# Sheet1.net
KiCad netlist of a schematic drawn in Altium Designer
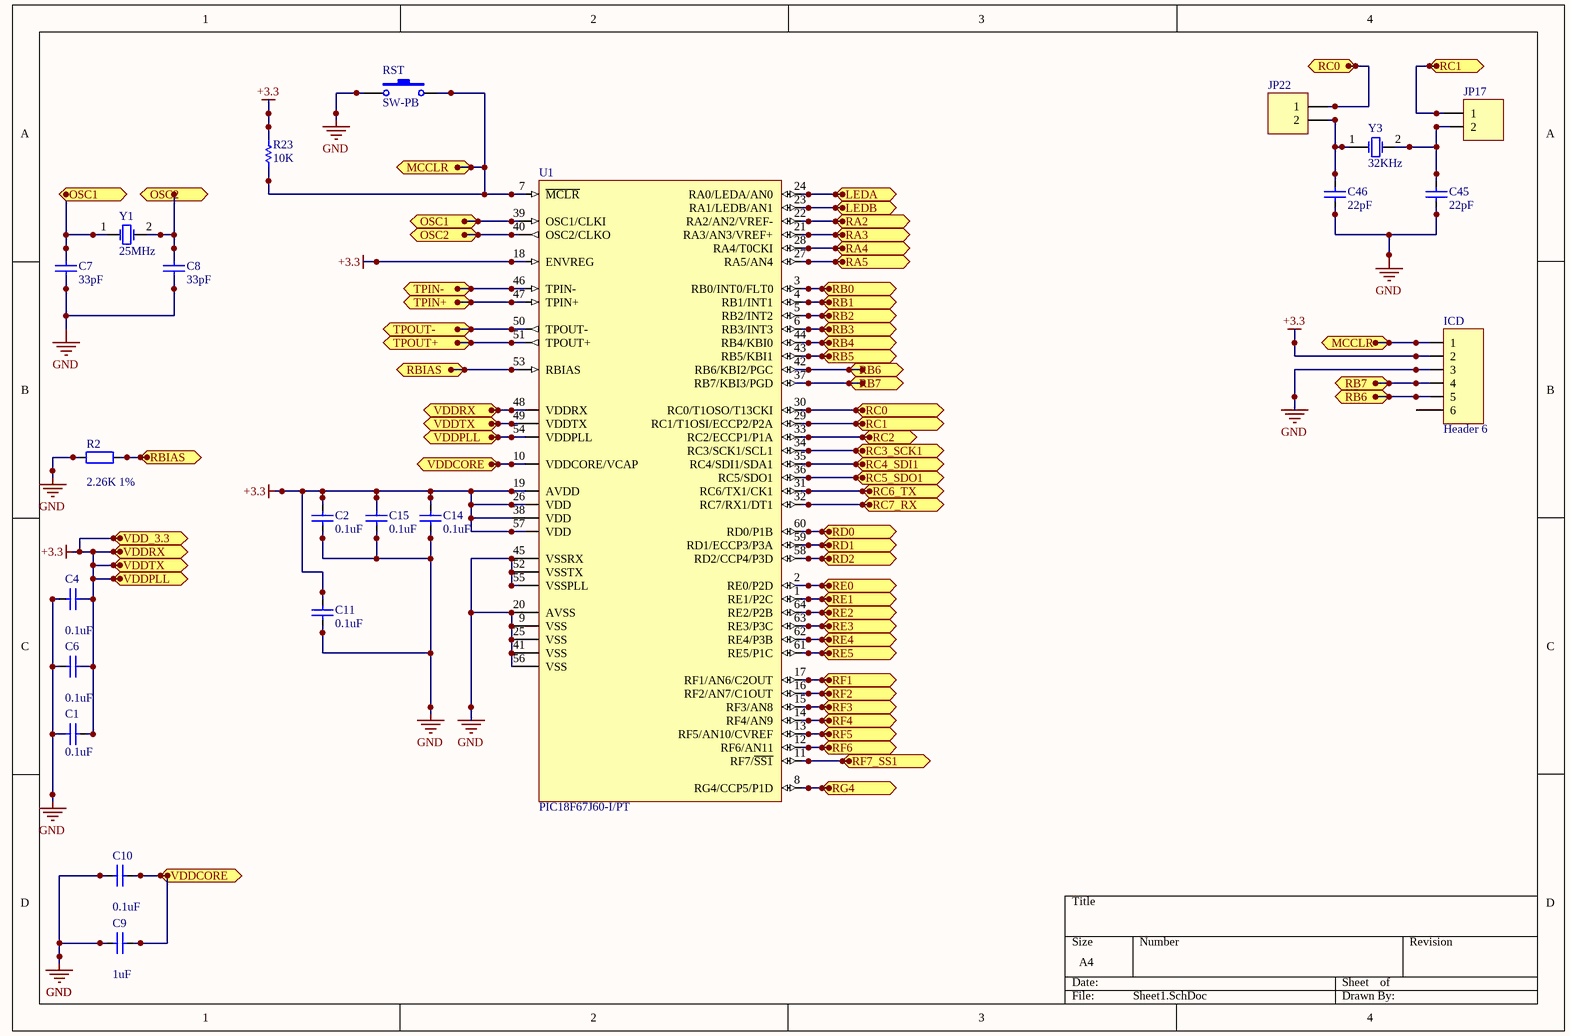
[diagram p0: Sheet1.SchDoc]

(export (version "E")
  (design (tool "Eeschema 10.0.6"))
  (components
    (comp (ref "C1")
      (value "0.1uF")
      (footprint "CAPC2012L")
      (description "Capacitor (Semiconductor SIM Model)")
      (fields (field (name "PUBLISHER") "Altium Limited"))
      (libsource (lib "Miscellaneous Devices") (part "Cap Semi"))
    )
    (comp (ref "C2")
      (value "0.1uF")
      (footprint "CAPC2012L")
      (description "Capacitor")
      (fields (field (name "PUBLISHER") "Altium Limited"))
      (libsource (lib "Miscellaneous Devices") (part "Cap"))
    )
    (comp (ref "C4")
      (value "0.1uF")
      (footprint "CAPC2012L")
      (description "Capacitor")
      (fields (field (name "PUBLISHER") "Altium Limited"))
      (libsource (lib "Miscellaneous Devices") (part "Cap"))
    )
    (comp (ref "C6")
      (value "0.1uF")
      (footprint "CAPC2012L")
      (description "Capacitor")
      (fields (field (name "PUBLISHER") "Altium Limited"))
      (libsource (lib "Miscellaneous Devices") (part "Cap"))
    )
    (comp (ref "C7")
      (value "33pF")
      (footprint "CAPC2012L")
      (description "Capacitor")
      (fields (field (name "PUBLISHER") "Altium Limited"))
      (libsource (lib "Miscellaneous Devices") (part "Cap"))
    )
    (comp (ref "C8")
      (value "33pF")
      (footprint "CAPC2012L")
      (description "Capacitor")
      (fields (field (name "PUBLISHER") "Altium Limited"))
      (libsource (lib "Miscellaneous Devices") (part "Cap"))
    )
    (comp (ref "C9")
      (value "1uF")
      (footprint "CAPC2012L")
      (description "Capacitor")
      (fields (field (name "PUBLISHER") "Altium Limited"))
      (libsource (lib "Miscellaneous Devices") (part "Cap"))
    )
    (comp (ref "C10")
      (value "0.1uF")
      (footprint "CAPC2012L")
      (description "Capacitor")
      (fields (field (name "PUBLISHER") "Altium Limited"))
      (libsource (lib "Miscellaneous Devices") (part "Cap"))
    )
    (comp (ref "C11")
      (value "0.1uF")
      (footprint "CAPC2012L")
      (description "Capacitor")
      (fields (field (name "PUBLISHER") "Altium Limited"))
      (libsource (lib "Miscellaneous Devices") (part "Cap"))
    )
    (comp (ref "C14")
      (value "0.1uF")
      (footprint "CAPC2012L")
      (description "Capacitor")
      (fields (field (name "PUBLISHER") "Altium Limited"))
      (libsource (lib "Miscellaneous Devices") (part "Cap"))
    )
    (comp (ref "C15")
      (value "0.1uF")
      (footprint "CAPC2012L")
      (description "Capacitor")
      (fields (field (name "PUBLISHER") "Altium Limited"))
      (libsource (lib "Miscellaneous Devices") (part "Cap"))
    )
    (comp (ref "C45")
      (value "22pF")
      (footprint "CAPC2012L")
      (description "Capacitor (Semiconductor SIM Model)")
      (fields (field (name "PUBLISHER") "Altium Limited"))
      (libsource (lib "Miscellaneous Devices") (part "Cap Semi"))
    )
    (comp (ref "C46")
      (value "22pF")
      (footprint "CAPC2012L")
      (description "Capacitor (Semiconductor SIM Model)")
      (fields (field (name "PUBLISHER") "Altium Limited"))
      (libsource (lib "Miscellaneous Devices") (part "Cap Semi"))
    )
    (comp (ref "ICD")
      (value "Header 6")
      (footprint "HDR1X6")
      (description "Header, 6-Pin")
      (fields (field (name "PUBLISHER") "Altium Limited"))
      (libsource (lib "Miscellaneous Connectors") (part "Header 6"))
    )
    (comp (ref "JP17")
      (value "Header 2")
      (footprint "HDR1X2")
      (description "Header, 2-Pin")
      (fields (field (name "PUBLISHER") "Altium Limited"))
      (libsource (lib "Miscellaneous Connectors") (part "Header 2"))
    )
    (comp (ref "JP22")
      (value "Header 2")
      (footprint "HDR1X2")
      (description "Header, 2-Pin")
      (fields (field (name "PUBLISHER") "Altium Limited"))
      (libsource (lib "") (part "Header 2_1"))
    )
    (comp (ref "R2")
      (value "2.26K 1%")
      (footprint "RESC2012L")
      (description "Resistor")
      (fields (field (name "PUBLISHER") "Altium Limited"))
      (libsource (lib "Miscellaneous Devices") (part "Res2"))
    )
    (comp (ref "R23")
      (value "10K")
      (footprint "RESC3216L")
      (description "Semiconductor Resistor")
      (fields (field (name "PUBLISHER") "Altium Limited"))
      (libsource (lib "Miscellaneous Devices") (part "Res Semi"))
    )
    (comp (ref "RST")
      (value "SW-PB")
      (footprint "SPST-2")
      (description "Switch")
      (fields (field (name "PUBLISHER") "Altium Limited"))
      (libsource (lib "Miscellaneous Devices") (part "SW-PB"))
    )
    (comp (ref "U1")
      (value "PIC18F67J60-I/PT")
      (footprint "TQFP-PT64_L")
      (fields (field (name "PUBLISHER") "Altium Limited"))
      (libsource (lib "Microchip Microcontroller 8-Bit PIC18") (part "PIC18F67J60-I/PT"))
    )
    (comp (ref "Y1")
      (value "25MHz")
      (footprint "SPST-2")
      (description "Crystal Oscillator")
      (fields (field (name "PUBLISHER") "Altium Limited"))
      (libsource (lib "Miscellaneous Devices") (part "XTAL"))
    )
    (comp (ref "Y3")
      (value "32KHz")
      (footprint "SPST-2")
      (description "Crystal Oscillator")
      (fields (field (name "PUBLISHER") "Altium Limited"))
      (libsource (lib "Miscellaneous Devices") (part "XTAL"))
    )
  )
  (nets
    (net (code "1") (name "+3.3") (class "Default")
      (node (ref "C1") (pin "2") (pinfunction "2_2") (pintype "passive"))
      (node (ref "C11") (pin "2") (pinfunction "2_2") (pintype "passive"))
      (node (ref "C14") (pin "2") (pinfunction "2_2") (pintype "passive"))
      (node (ref "C15") (pin "2") (pinfunction "2_2") (pintype "passive"))
      (node (ref "C2") (pin "2") (pinfunction "2_2") (pintype "passive"))
      (node (ref "C4") (pin "2") (pinfunction "2_2") (pintype "passive"))
      (node (ref "C6") (pin "2") (pinfunction "2_2") (pintype "passive"))
      (node (ref "ICD") (pin "2") (pinfunction "2_2") (pintype "passive"))
      (node (ref "R23") (pin "2") (pinfunction "2_2") (pintype "passive"))
      (node (ref "U1") (pin "18") (pinfunction "ENVREG_18") (pintype "input"))
      (node (ref "U1") (pin "19") (pinfunction "AVDD_19") (pintype "power_in"))
      (node (ref "U1") (pin "26") (pinfunction "VDD_26") (pintype "power_in"))
      (node (ref "U1") (pin "38") (pinfunction "VDD_38") (pintype "power_in"))
      (node (ref "U1") (pin "48") (pinfunction "VDDRX_48") (pintype "power_in"))
      (node (ref "U1") (pin "49") (pinfunction "VDDTX_49") (pintype "power_in"))
      (node (ref "U1") (pin "54") (pinfunction "VDDPLL_54") (pintype "power_in"))
      (node (ref "U1") (pin "57") (pinfunction "VDD_57") (pintype "power_in"))
    )
    (net (code "2") (name "/LEDA") (class "Default")
      (node (ref "U1") (pin "24") (pinfunction "RA0/LEDA/AN0_24") (pintype "bidirectional"))
    )
    (net (code "3") (name "/LEDB") (class "Default")
      (node (ref "U1") (pin "23") (pinfunction "RA1/LEDB/AN1_23") (pintype "bidirectional"))
    )
    (net (code "4") (name "/MCCLR") (class "Default")
      (node (ref "ICD") (pin "1") (pinfunction "1_1") (pintype "passive"))
      (node (ref "R23") (pin "1") (pinfunction "1_1") (pintype "passive"))
      (node (ref "RST") (pin "2") (pinfunction "2_2") (pintype "passive"))
      (node (ref "U1") (pin "7") (pinfunction "~{MCLR}_7") (pintype "input"))
    )
    (net (code "5") (name "/OSC1") (class "Default")
      (node (ref "U1") (pin "39") (pinfunction "OSC1/CLKI_39") (pintype "input"))
    )
    (net (code "6") (name "/OSC2") (class "Default")
      (node (ref "U1") (pin "40") (pinfunction "OSC2/CLKO_40") (pintype "output"))
    )
    (net (code "7") (name "/RA2") (class "Default")
      (node (ref "U1") (pin "22") (pinfunction "RA2/AN2/VREF-_22") (pintype "bidirectional"))
    )
    (net (code "8") (name "/RA3") (class "Default")
      (node (ref "U1") (pin "21") (pinfunction "RA3/AN3/VREF+_21") (pintype "bidirectional"))
    )
    (net (code "9") (name "/RA4") (class "Default")
      (node (ref "U1") (pin "28") (pinfunction "RA4/T0CKI_28") (pintype "bidirectional"))
    )
    (net (code "10") (name "/RA5") (class "Default")
      (node (ref "U1") (pin "27") (pinfunction "RA5/AN4_27") (pintype "bidirectional"))
    )
    (net (code "11") (name "/RB0") (class "Default")
      (node (ref "U1") (pin "3") (pinfunction "RB0/INT0/FLT0_3") (pintype "bidirectional"))
    )
    (net (code "12") (name "/RB1") (class "Default")
      (node (ref "U1") (pin "4") (pinfunction "RB1/INT1_4") (pintype "bidirectional"))
    )
    (net (code "13") (name "/RB2") (class "Default")
      (node (ref "U1") (pin "5") (pinfunction "RB2/INT2_5") (pintype "bidirectional"))
    )
    (net (code "14") (name "/RB3") (class "Default")
      (node (ref "U1") (pin "6") (pinfunction "RB3/INT3_6") (pintype "bidirectional"))
    )
    (net (code "15") (name "/RB4") (class "Default")
      (node (ref "U1") (pin "44") (pinfunction "RB4/KBI0_44") (pintype "bidirectional"))
    )
    (net (code "16") (name "/RB5") (class "Default")
      (node (ref "U1") (pin "43") (pinfunction "RB5/KBI1_43") (pintype "bidirectional"))
    )
    (net (code "17") (name "/RB6") (class "Default")
      (node (ref "ICD") (pin "5") (pinfunction "5_5") (pintype "passive"))
      (node (ref "U1") (pin "42") (pinfunction "RB6/KBI2/PGC_42") (pintype "bidirectional"))
    )
    (net (code "18") (name "/RB7") (class "Default")
      (node (ref "ICD") (pin "4") (pinfunction "4_4") (pintype "passive"))
      (node (ref "U1") (pin "37") (pinfunction "RB7/KBI3/PGD_37") (pintype "bidirectional"))
    )
    (net (code "19") (name "/RBIAS") (class "Default")
      (node (ref "R2") (pin "2") (pinfunction "2_2") (pintype "passive"))
      (node (ref "U1") (pin "53") (pinfunction "RBIAS_53") (pintype "input"))
    )
    (net (code "20") (name "/RC0") (class "Default")
      (node (ref "JP22") (pin "1") (pinfunction "1_1") (pintype "passive"))
      (node (ref "U1") (pin "30") (pinfunction "RC0/T1OSO/T13CKI_30") (pintype "bidirectional"))
    )
    (net (code "21") (name "/RC1") (class "Default")
      (node (ref "JP17") (pin "1") (pinfunction "1_1") (pintype "passive"))
      (node (ref "U1") (pin "29") (pinfunction "RC1/T1OSI/ECCP2/P2A_29") (pintype "bidirectional"))
    )
    (net (code "22") (name "/RC2") (class "Default")
      (node (ref "U1") (pin "33") (pinfunction "RC2/ECCP1/P1A_33") (pintype "bidirectional"))
    )
    (net (code "23") (name "/RC3_SCK1") (class "Default")
      (node (ref "U1") (pin "34") (pinfunction "RC3/SCK1/SCL1_34") (pintype "bidirectional"))
    )
    (net (code "24") (name "/RC4_SDI1") (class "Default")
      (node (ref "U1") (pin "35") (pinfunction "RC4/SDI1/SDA1_35") (pintype "bidirectional"))
    )
    (net (code "25") (name "/RC5_SDO1") (class "Default")
      (node (ref "U1") (pin "36") (pinfunction "RC5/SDO1_36") (pintype "bidirectional"))
    )
    (net (code "26") (name "/RC6_TX") (class "Default")
      (node (ref "U1") (pin "31") (pinfunction "RC6/TX1/CK1_31") (pintype "bidirectional"))
    )
    (net (code "27") (name "/RC7_RX") (class "Default")
      (node (ref "U1") (pin "32") (pinfunction "RC7/RX1/DT1_32") (pintype "bidirectional"))
    )
    (net (code "28") (name "/RD0") (class "Default")
      (node (ref "U1") (pin "60") (pinfunction "RD0/P1B_60") (pintype "bidirectional"))
    )
    (net (code "29") (name "/RD1") (class "Default")
      (node (ref "U1") (pin "59") (pinfunction "RD1/ECCP3/P3A_59") (pintype "bidirectional"))
    )
    (net (code "30") (name "/RD2") (class "Default")
      (node (ref "U1") (pin "58") (pinfunction "RD2/CCP4/P3D_58") (pintype "bidirectional"))
    )
    (net (code "31") (name "/RE0") (class "Default")
      (node (ref "U1") (pin "2") (pinfunction "RE0/P2D_2") (pintype "bidirectional"))
    )
    (net (code "32") (name "/RE1") (class "Default")
      (node (ref "U1") (pin "1") (pinfunction "RE1/P2C_1") (pintype "bidirectional"))
    )
    (net (code "33") (name "/RE2") (class "Default")
      (node (ref "U1") (pin "64") (pinfunction "RE2/P2B_64") (pintype "bidirectional"))
    )
    (net (code "34") (name "/RE3") (class "Default")
      (node (ref "U1") (pin "63") (pinfunction "RE3/P3C_63") (pintype "bidirectional"))
    )
    (net (code "35") (name "/RE4") (class "Default")
      (node (ref "U1") (pin "62") (pinfunction "RE4/P3B_62") (pintype "bidirectional"))
    )
    (net (code "36") (name "/RE5") (class "Default")
      (node (ref "U1") (pin "61") (pinfunction "RE5/P1C_61") (pintype "bidirectional"))
    )
    (net (code "37") (name "/RF1") (class "Default")
      (node (ref "U1") (pin "17") (pinfunction "RF1/AN6/C2OUT_17") (pintype "bidirectional"))
    )
    (net (code "38") (name "/RF2") (class "Default")
      (node (ref "U1") (pin "16") (pinfunction "RF2/AN7/C1OUT_16") (pintype "bidirectional"))
    )
    (net (code "39") (name "/RF3") (class "Default")
      (node (ref "U1") (pin "15") (pinfunction "RF3/AN8_15") (pintype "bidirectional"))
    )
    (net (code "40") (name "/RF4") (class "Default")
      (node (ref "U1") (pin "14") (pinfunction "RF4/AN9_14") (pintype "bidirectional"))
    )
    (net (code "41") (name "/RF5") (class "Default")
      (node (ref "U1") (pin "13") (pinfunction "RF5/AN10/CVREF_13") (pintype "bidirectional"))
    )
    (net (code "42") (name "/RF6") (class "Default")
      (node (ref "U1") (pin "12") (pinfunction "RF6/AN11_12") (pintype "bidirectional"))
    )
    (net (code "43") (name "/RF7_SS1") (class "Default")
      (node (ref "U1") (pin "11") (pinfunction "RF7/~{SS1}_11") (pintype "bidirectional"))
    )
    (net (code "44") (name "/RG4") (class "Default")
      (node (ref "U1") (pin "8") (pinfunction "RG4/CCP5/P1D_8") (pintype "bidirectional"))
    )
    (net (code "45") (name "/TPIN+") (class "Default")
      (node (ref "U1") (pin "47") (pinfunction "TPIN+_47") (pintype "input"))
    )
    (net (code "46") (name "/TPIN-") (class "Default")
      (node (ref "U1") (pin "46") (pinfunction "TPIN-_46") (pintype "input"))
    )
    (net (code "47") (name "/TPOUT+") (class "Default")
      (node (ref "U1") (pin "51") (pinfunction "TPOUT+_51") (pintype "output"))
    )
    (net (code "48") (name "/TPOUT-") (class "Default")
      (node (ref "U1") (pin "50") (pinfunction "TPOUT-_50") (pintype "output"))
    )
    (net (code "49") (name "/VDDCORE") (class "Default")
      (node (ref "C10") (pin "2") (pinfunction "2_2") (pintype "passive"))
      (node (ref "C9") (pin "2") (pinfunction "2_2") (pintype "passive"))
      (node (ref "U1") (pin "10") (pinfunction "VDDCORE/VCAP_10") (pintype "power_in"))
    )
    (net (code "50") (name "GND") (class "Default")
      (node (ref "C1") (pin "1") (pinfunction "1_1") (pintype "passive"))
      (node (ref "C10") (pin "1") (pinfunction "1_1") (pintype "passive"))
      (node (ref "C11") (pin "1") (pinfunction "1_1") (pintype "passive"))
      (node (ref "C14") (pin "1") (pinfunction "1_1") (pintype "passive"))
      (node (ref "C15") (pin "1") (pinfunction "1_1") (pintype "passive"))
      (node (ref "C2") (pin "1") (pinfunction "1_1") (pintype "passive"))
      (node (ref "C4") (pin "1") (pinfunction "1_1") (pintype "passive"))
      (node (ref "C45") (pin "1") (pinfunction "1_1") (pintype "passive"))
      (node (ref "C46") (pin "1") (pinfunction "1_1") (pintype "passive"))
      (node (ref "C6") (pin "1") (pinfunction "1_1") (pintype "passive"))
      (node (ref "C7") (pin "1") (pinfunction "1_1") (pintype "passive"))
      (node (ref "C8") (pin "1") (pinfunction "1_1") (pintype "passive"))
      (node (ref "C9") (pin "1") (pinfunction "1_1") (pintype "passive"))
      (node (ref "ICD") (pin "3") (pinfunction "3_3") (pintype "passive"))
      (node (ref "R2") (pin "1") (pinfunction "1_1") (pintype "passive"))
      (node (ref "RST") (pin "1") (pinfunction "1_1") (pintype "passive"))
      (node (ref "U1") (pin "20") (pinfunction "AVSS_20") (pintype "power_in"))
      (node (ref "U1") (pin "25") (pinfunction "VSS_25") (pintype "power_in"))
      (node (ref "U1") (pin "41") (pinfunction "VSS_41") (pintype "power_in"))
      (node (ref "U1") (pin "45") (pinfunction "VSSRX_45") (pintype "power_in"))
      (node (ref "U1") (pin "52") (pinfunction "VSSTX_52") (pintype "power_in"))
      (node (ref "U1") (pin "55") (pinfunction "VSSPLL_55") (pintype "power_in"))
      (node (ref "U1") (pin "56") (pinfunction "VSS_56") (pintype "power_in"))
      (node (ref "U1") (pin "9") (pinfunction "VSS_9") (pintype "power_in"))
    )
    (net (code "51") (name "Net-(Y1-OSC1)") (class "Default")
      (node (ref "C7") (pin "2") (pinfunction "2_2") (pintype "passive"))
      (node (ref "Y1") (pin "1") (pinfunction "OSC1_1") (pintype "passive"))
    )
    (net (code "52") (name "Net-(Y1-OSC2)") (class "Default")
      (node (ref "C8") (pin "2") (pinfunction "2_2") (pintype "passive"))
      (node (ref "Y1") (pin "2") (pinfunction "OSC2_2") (pintype "passive"))
    )
    (net (code "53") (name "Net-(Y3-OSC1)") (class "Default")
      (node (ref "C46") (pin "2") (pinfunction "2_2") (pintype "passive"))
      (node (ref "JP22") (pin "2") (pinfunction "2_2") (pintype "passive"))
      (node (ref "Y3") (pin "1") (pinfunction "OSC1_1") (pintype "passive"))
    )
    (net (code "54") (name "Net-(Y3-OSC2)") (class "Default")
      (node (ref "C45") (pin "2") (pinfunction "2_2") (pintype "passive"))
      (node (ref "JP17") (pin "2") (pinfunction "2_2") (pintype "passive"))
      (node (ref "Y3") (pin "2") (pinfunction "OSC2_2") (pintype "passive"))
    )
    (net (code "55") (name "unconnected-(ICD-Pad6)") (class "Default")
      (node (ref "ICD") (pin "6") (pinfunction "6_6") (pintype "passive"))
    )
  )
)
